# horse_relay.net
KiCad netlist of a schematic drawn in EAGLE
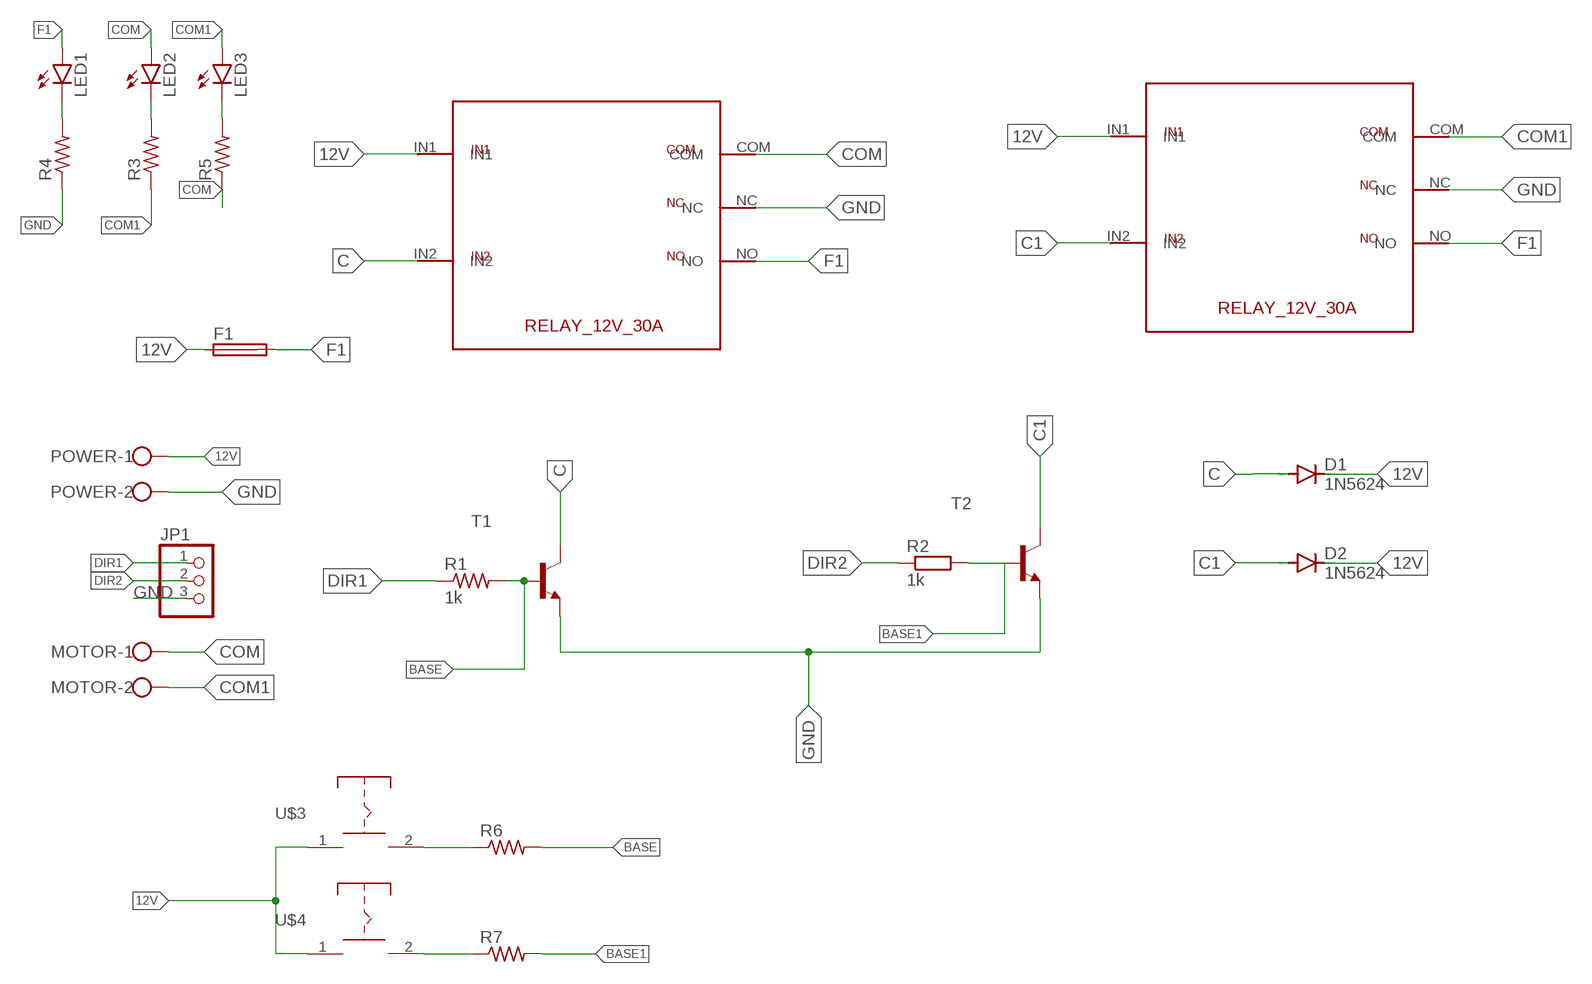
[diagram p0: schematic, sheet 1]

(export (version "E")
  (design (tool "Eeschema 10.0.6"))
  (components
    (comp (ref "D1")
      (value "1N5624")
      (footprint "eagle-import:DO201-15")
      (libsource (lib "eagle-import") (part "1N5624"))
    )
    (comp (ref "D2")
      (value "1N5624")
      (footprint "eagle-import:DO201-15")
      (libsource (lib "eagle-import") (part "1N5624"))
    )
    (comp (ref "F1")
      (value "SH22,5A")
      (footprint "eagle-import:SH22,5A")
      (fields (field (name "MPN") "0031.7701.11"))
      (libsource (lib "eagle-import") (part "SH22,5A"))
    )
    (comp (ref "JP1")
      (value "PINHD-1X3")
      (footprint "eagle-import:1X03")
      (libsource (lib "eagle-import") (part "PINHD-1X3"))
    )
    (comp (ref "LED1")
      (value "LED5MM")
      (footprint "eagle-import:LED5MM")
      (libsource (lib "eagle-import") (part "LED5MM"))
    )
    (comp (ref "LED2")
      (value "LED3MM")
      (footprint "eagle-import:LED3MM")
      (libsource (lib "eagle-import") (part "LED3MM"))
    )
    (comp (ref "LED3")
      (value "LED3MM")
      (footprint "eagle-import:LED3MM")
      (libsource (lib "eagle-import") (part "LED3MM"))
    )
    (comp (ref "MOTOR")
      (value "W237-113")
      (footprint "eagle-import:W237-113")
      (libsource (lib "eagle-import") (part "W237-113"))
    )
    (comp (ref "POWER")
      (value "W237-113")
      (footprint "eagle-import:W237-113")
      (libsource (lib "eagle-import") (part "W237-113"))
    )
    (comp (ref "R1")
      (value "1k")
      (footprint "eagle-import:0207_10")
      (libsource (lib "eagle-import") (part "R-US_0207/10"))
    )
    (comp (ref "R2")
      (value "1k")
      (footprint "eagle-import:0204_7")
      (libsource (lib "eagle-import") (part "R-EU_0204/7"))
    )
    (comp (ref "R3")
      (value "R-US_0207/12")
      (footprint "eagle-import:0207_12")
      (libsource (lib "eagle-import") (part "R-US_0207/12"))
    )
    (comp (ref "R4")
      (value "R-US_0204/7")
      (footprint "eagle-import:0204_7")
      (libsource (lib "eagle-import") (part "R-US_0204/7"))
    )
    (comp (ref "R5")
      (value "R-US_0207/15")
      (footprint "eagle-import:0207_15")
      (libsource (lib "eagle-import") (part "R-US_0207/15"))
    )
    (comp (ref "R6")
      (value "R-US_0207/12")
      (footprint "eagle-import:0207_12")
      (libsource (lib "eagle-import") (part "R-US_0207/12"))
    )
    (comp (ref "R7")
      (value "R-US_0204/7")
      (footprint "eagle-import:0204_7")
      (libsource (lib "eagle-import") (part "R-US_0204/7"))
    )
    (comp (ref "T1")
      (value "2N3904-NPN-TO92-EBC")
      (footprint "eagle-import:TO92-EBC")
      (libsource (lib "eagle-import") (part "-NPN-TO92-EBC2N3904"))
    )
    (comp (ref "T2")
      (value "2N3904-NPN-TO92-EBC")
      (footprint "eagle-import:TO92-EBC")
      (libsource (lib "eagle-import") (part "-NPN-TO92-EBC2N3904"))
    )
    (comp (ref "U$1")
      (value "RELAY_12V_30A")
      (footprint "eagle-import:RELAY_12V_30A")
      (libsource (lib "eagle-import") (part "RELAY_12V_30A"))
    )
    (comp (ref "U$2")
      (value "RELAY_12V_30A")
      (footprint "eagle-import:RELAY_12V_30A")
      (libsource (lib "eagle-import") (part "RELAY_12V_30A"))
    )
    (comp (ref "U$3")
      (value "PUSHBOTTON")
      (footprint "eagle-import:PUSHBOTTON")
      (libsource (lib "eagle-import") (part "PUSHBOTTON"))
    )
    (comp (ref "U$4")
      (value "PUSHBOTTON")
      (footprint "eagle-import:PUSHBOTTON")
      (libsource (lib "eagle-import") (part "PUSHBOTTON"))
    )
  )
  (nets
    (net (code "1") (name "12V") (class "Default")
      (node (ref "D1") (pin "C") (pinfunction "C_C") (pintype "passive"))
      (node (ref "D2") (pin "C") (pinfunction "C_C") (pintype "passive"))
      (node (ref "F1") (pin "1") (pinfunction "1_1") (pintype "passive"))
      (node (ref "POWER") (pin "1") (pinfunction "KL_1") (pintype "passive"))
      (node (ref "U$1") (pin "IN1") (pinfunction "IN1_IN1") (pintype "bidirectional"))
      (node (ref "U$2") (pin "IN1") (pinfunction "IN1_IN1") (pintype "bidirectional"))
      (node (ref "U$3") (pin "1") (pinfunction "1_1") (pintype "bidirectional"))
      (node (ref "U$4") (pin "1") (pinfunction "1_1") (pintype "bidirectional"))
    )
    (net (code "2") (name "BASE") (class "Default")
      (node (ref "R1") (pin "2") (pinfunction "2_2") (pintype "passive"))
      (node (ref "R6") (pin "2") (pinfunction "2_2") (pintype "passive"))
      (node (ref "T1") (pin "B") (pinfunction "B_B") (pintype "passive"))
    )
    (net (code "3") (name "BASE1") (class "Default")
      (node (ref "R2") (pin "2") (pinfunction "2_2") (pintype "passive"))
      (node (ref "R7") (pin "2") (pinfunction "2_2") (pintype "passive"))
      (node (ref "T2") (pin "B") (pinfunction "B_B") (pintype "passive"))
    )
    (net (code "4") (name "C") (class "Default")
      (node (ref "D1") (pin "A") (pinfunction "A_A") (pintype "passive"))
      (node (ref "T1") (pin "C") (pinfunction "C_C") (pintype "passive"))
      (node (ref "U$1") (pin "IN2") (pinfunction "IN2_IN2") (pintype "bidirectional"))
    )
    (net (code "5") (name "C1") (class "Default")
      (node (ref "D2") (pin "A") (pinfunction "A_A") (pintype "passive"))
      (node (ref "T2") (pin "C") (pinfunction "C_C") (pintype "passive"))
      (node (ref "U$2") (pin "IN2") (pinfunction "IN2_IN2") (pintype "bidirectional"))
    )
    (net (code "6") (name "COM") (class "Default")
      (node (ref "LED2") (pin "A") (pinfunction "A_A") (pintype "passive"))
      (node (ref "MOTOR") (pin "1") (pinfunction "KL_1") (pintype "passive"))
      (node (ref "R5") (pin "1") (pinfunction "1_1") (pintype "passive"))
      (node (ref "U$1") (pin "COM") (pinfunction "COM_COM") (pintype "bidirectional"))
    )
    (net (code "7") (name "COM1") (class "Default")
      (node (ref "LED3") (pin "A") (pinfunction "A_A") (pintype "passive"))
      (node (ref "MOTOR") (pin "2") (pinfunction "KL_2") (pintype "passive"))
      (node (ref "R3") (pin "1") (pinfunction "1_1") (pintype "passive"))
      (node (ref "U$2") (pin "COM") (pinfunction "COM_COM") (pintype "bidirectional"))
    )
    (net (code "8") (name "DIR1") (class "Default")
      (node (ref "JP1") (pin "1") (pinfunction "1_1") (pintype "passive"))
      (node (ref "R1") (pin "1") (pinfunction "1_1") (pintype "passive"))
    )
    (net (code "9") (name "DIR2") (class "Default")
      (node (ref "JP1") (pin "2") (pinfunction "2_2") (pintype "passive"))
      (node (ref "R2") (pin "1") (pinfunction "1_1") (pintype "passive"))
    )
    (net (code "10") (name "F1") (class "Default")
      (node (ref "F1") (pin "2") (pinfunction "2_2") (pintype "passive"))
      (node (ref "LED1") (pin "A") (pinfunction "A_A") (pintype "passive"))
      (node (ref "U$1") (pin "NO") (pinfunction "NO_NO") (pintype "bidirectional"))
      (node (ref "U$2") (pin "NO") (pinfunction "NO_NO") (pintype "bidirectional"))
    )
    (net (code "11") (name "GND") (class "Default")
      (node (ref "JP1") (pin "3") (pinfunction "3_3") (pintype "passive"))
      (node (ref "POWER") (pin "2") (pinfunction "KL_2") (pintype "passive"))
      (node (ref "R4") (pin "1") (pinfunction "1_1") (pintype "passive"))
      (node (ref "T1") (pin "E") (pinfunction "E_E") (pintype "passive"))
      (node (ref "T2") (pin "E") (pinfunction "E_E") (pintype "passive"))
      (node (ref "U$1") (pin "NC") (pinfunction "NC_NC") (pintype "bidirectional"))
      (node (ref "U$2") (pin "NC") (pinfunction "NC_NC") (pintype "bidirectional"))
    )
    (net (code "12") (name "Net-(LED1-C)") (class "Default")
      (node (ref "LED1") (pin "K") (pinfunction "C_K") (pintype "passive"))
      (node (ref "R4") (pin "2") (pinfunction "2_2") (pintype "passive"))
    )
    (net (code "13") (name "Net-(LED2-C)") (class "Default")
      (node (ref "LED2") (pin "K") (pinfunction "C_K") (pintype "passive"))
      (node (ref "R3") (pin "2") (pinfunction "2_2") (pintype "passive"))
    )
    (net (code "14") (name "Net-(LED3-C)") (class "Default")
      (node (ref "LED3") (pin "K") (pinfunction "C_K") (pintype "passive"))
      (node (ref "R5") (pin "2") (pinfunction "2_2") (pintype "passive"))
    )
    (net (code "15") (name "Net-(R6-Pad1)") (class "Default")
      (node (ref "R6") (pin "1") (pinfunction "1_1") (pintype "passive"))
      (node (ref "U$3") (pin "2") (pinfunction "2_2") (pintype "bidirectional"))
    )
    (net (code "16") (name "Net-(R7-Pad1)") (class "Default")
      (node (ref "R7") (pin "1") (pinfunction "1_1") (pintype "passive"))
      (node (ref "U$4") (pin "2") (pinfunction "2_2") (pintype "bidirectional"))
    )
  )
)
